# working.net
KiCad netlist of a schematic drawn in EAGLE
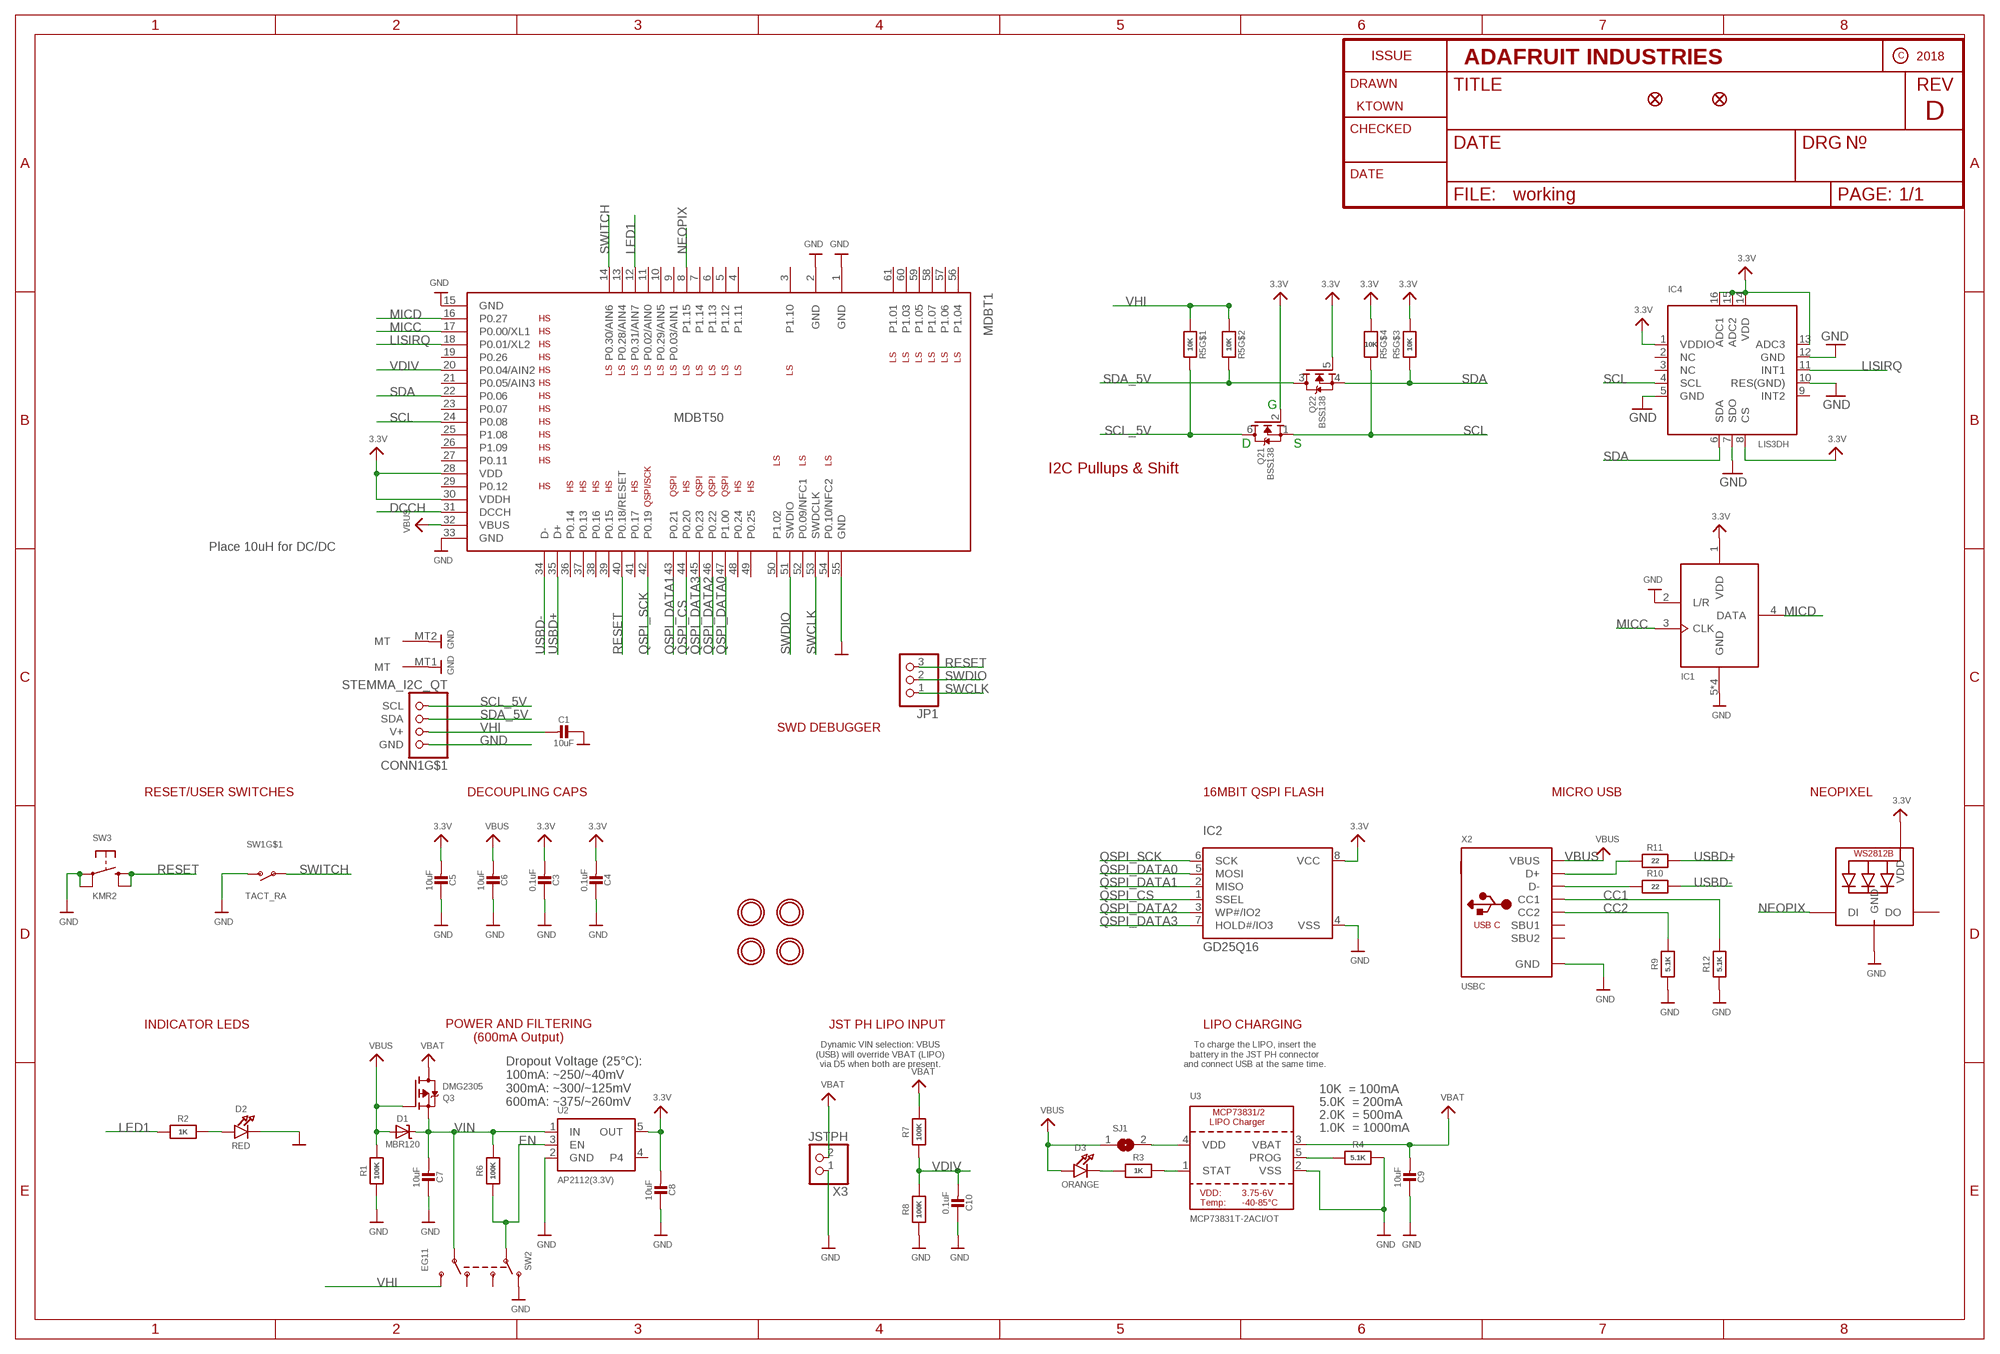
[diagram p0: schematic, sheet 1]

(export (version "E")
  (design (tool "Eeschema 10.0.6"))
  (components
    (comp (ref "C1")
      (value "10uF")
      (footprint "eagle-import:0805-NO")
      (libsource (lib "eagle-import") (part "CAP_CERAMIC0805-NOOUTLINE"))
    )
    (comp (ref "C3")
      (value "0.1uF")
      (footprint "eagle-import:0603-NO")
      (libsource (lib "eagle-import") (part "CAP_CERAMIC0603_NO"))
    )
    (comp (ref "C4")
      (value "0.1uF")
      (footprint "eagle-import:0603-NO")
      (libsource (lib "eagle-import") (part "CAP_CERAMIC0603_NO"))
    )
    (comp (ref "C5")
      (value "10uF")
      (footprint "eagle-import:0805-NO")
      (libsource (lib "eagle-import") (part "CAP_CERAMIC0805-NOOUTLINE"))
    )
    (comp (ref "C6")
      (value "10uF")
      (footprint "eagle-import:0805-NO")
      (libsource (lib "eagle-import") (part "CAP_CERAMIC0805-NOOUTLINE"))
    )
    (comp (ref "C7")
      (value "10uF")
      (footprint "eagle-import:0805-NO")
      (libsource (lib "eagle-import") (part "CAP_CERAMIC0805-NOOUTLINE"))
    )
    (comp (ref "C8")
      (value "10uF")
      (footprint "eagle-import:0805-NO")
      (libsource (lib "eagle-import") (part "CAP_CERAMIC0805-NOOUTLINE"))
    )
    (comp (ref "C9")
      (value "10uF")
      (footprint "eagle-import:0805-NO")
      (libsource (lib "eagle-import") (part "CAP_CERAMIC0805-NOOUTLINE"))
    )
    (comp (ref "C10")
      (value "0.1uF")
      (footprint "eagle-import:0603-NO")
      (libsource (lib "eagle-import") (part "CAP_CERAMIC0603_NO"))
    )
    (comp (ref "CONN1")
      (value "STEMMA_I2C_QT")
      (footprint "eagle-import:JST_SH4")
      (libsource (lib "eagle-import") (part "STEMMA_I2C_QT"))
    )
    (comp (ref "D1")
      (value "MBR120")
      (footprint "eagle-import:SOD-123")
      (libsource (lib "eagle-import") (part "DIODE-SCHOTTKYSOD-123"))
    )
    (comp (ref "D2")
      (value "RED")
      (footprint "eagle-import:CHIPLED_0805_NOOUTLINE")
      (libsource (lib "eagle-import") (part "LED0805_NOOUTLINE"))
    )
    (comp (ref "D3")
      (value "ORANGE")
      (footprint "eagle-import:CHIPLED_0805_NOOUTLINE")
      (libsource (lib "eagle-import") (part "LED0805_NOOUTLINE"))
    )
    (comp (ref "FID1")
      (value "FIDUCIAL_1MM")
      (footprint "eagle-import:FIDUCIAL_1MM")
      (libsource (lib "eagle-import") (part "FIDUCIAL_1MM"))
    )
    (comp (ref "FID2")
      (value "FIDUCIAL_1MM")
      (footprint "eagle-import:FIDUCIAL_1MM")
      (libsource (lib "eagle-import") (part "FIDUCIAL_1MM"))
    )
    (comp (ref "IC1")
      (value "MIC_PDM_SPK0415")
      (footprint "eagle-import:SPK0415HM4H")
      (libsource (lib "eagle-import") (part "MIC_PDM_SPK0415"))
    )
    (comp (ref "IC2")
      (value "GD25Q16")
      (footprint "eagle-import:SOIC8_150MIL")
      (libsource (lib "eagle-import") (part "SPIFLASH_8PIN"))
    )
    (comp (ref "IC4")
      (value "LIS3DH")
      (footprint "eagle-import:LGA16_3X3MM")
      (libsource (lib "eagle-import") (part "ACCEL_LIS3DHTR"))
    )
    (comp (ref "JP1")
      (value "HEADER-1X3ROUND")
      (footprint "eagle-import:1X03_ROUND")
      (libsource (lib "eagle-import") (part "HEADER-1X3ROUND"))
    )
    (comp (ref "LED1")
      (value "WS2812B_SK6805_1515")
      (footprint "eagle-import:SK6805_1515")
      (libsource (lib "eagle-import") (part "WS2812B_SK6805_1515"))
    )
    (comp (ref "MDBT1")
      (value "MDBT50")
      (footprint "eagle-import:MDBT50")
      (libsource (lib "eagle-import") (part "MDBT50"))
    )
    (comp (ref "Q2")
      (value "BSS138")
      (footprint "eagle-import:SOT363")
      (libsource (lib "eagle-import") (part "MOSFET-N_DUAL"))
    )
    (comp (ref "Q3")
      (value "DMG2305")
      (footprint "eagle-import:SOT23-R")
      (libsource (lib "eagle-import") (part "MOSFET-P"))
    )
    (comp (ref "R1")
      (value "100K")
      (footprint "eagle-import:0603-NO")
      (libsource (lib "eagle-import") (part "RESISTOR_0603_NOOUT"))
    )
    (comp (ref "R2")
      (value "1K")
      (footprint "eagle-import:0603-NO")
      (libsource (lib "eagle-import") (part "RESISTOR_0603_NOOUT"))
    )
    (comp (ref "R3")
      (value "1K")
      (footprint "eagle-import:0603-NO")
      (libsource (lib "eagle-import") (part "RESISTOR_0603_NOOUT"))
    )
    (comp (ref "R4")
      (value "5.1K")
      (footprint "eagle-import:0603-NO")
      (libsource (lib "eagle-import") (part "RESISTOR_0603_NOOUT"))
    )
    (comp (ref "R5")
      (value "10K")
      (footprint "eagle-import:RESPACK_4X0603")
      (libsource (lib "eagle-import") (part "RESISTOR_4PACK"))
    )
    (comp (ref "R6")
      (value "100K")
      (footprint "eagle-import:0603-NO")
      (libsource (lib "eagle-import") (part "RESISTOR_0603_NOOUT"))
    )
    (comp (ref "R7")
      (value "100K")
      (footprint "eagle-import:0603-NO")
      (libsource (lib "eagle-import") (part "RESISTOR_0603_NOOUT"))
    )
    (comp (ref "R8")
      (value "100K")
      (footprint "eagle-import:0603-NO")
      (libsource (lib "eagle-import") (part "RESISTOR_0603_NOOUT"))
    )
    (comp (ref "R9")
      (value "5.1K")
      (footprint "eagle-import:0603-NO")
      (libsource (lib "eagle-import") (part "RESISTOR_0603_NOOUT"))
    )
    (comp (ref "R10")
      (value "22")
      (footprint "eagle-import:0603-NO")
      (libsource (lib "eagle-import") (part "RESISTOR_0603_NOOUT"))
    )
    (comp (ref "R11")
      (value "22")
      (footprint "eagle-import:0603-NO")
      (libsource (lib "eagle-import") (part "RESISTOR_0603_NOOUT"))
    )
    (comp (ref "R12")
      (value "5.1K")
      (footprint "eagle-import:0603-NO")
      (libsource (lib "eagle-import") (part "RESISTOR_0603_NOOUT"))
    )
    (comp (ref "SJ1")
      (value "SOLDERJUMPER")
      (footprint "eagle-import:SOLDERJUMPER_ARROW_NOPASTE")
      (libsource (lib "eagle-import") (part "SOLDERJUMPER"))
    )
    (comp (ref "SW1")
      (value "TACT_RA")
      (footprint "eagle-import:SPST_TACTILE_RA")
      (libsource (lib "eagle-import") (part "SWITCH_SPST_TACT_RA"))
    )
    (comp (ref "SW2")
      (value "EG11")
      (footprint "eagle-import:EG1390")
      (libsource (lib "eagle-import") (part "SWITCH_DPDTEG1390"))
    )
    (comp (ref "SW3")
      (value "KMR2")
      (footprint "eagle-import:BTN_KMR2_4.6X2.8")
      (libsource (lib "eagle-import") (part "SWITCH_TACT_SMT4.6X2.8"))
    )
    (comp (ref "U$10")
      (value "MOUNTINGHOLE_SLOT4MM")
      (footprint "eagle-import:SLOT_4MM_PLATED")
      (libsource (lib "eagle-import") (part "MOUNTINGHOLE_SLOT4MM"))
    )
    (comp (ref "U$12")
      (value "MOUNTINGHOLE_SLOT4MM")
      (footprint "eagle-import:SLOT_4MM_PLATED")
      (libsource (lib "eagle-import") (part "MOUNTINGHOLE_SLOT4MM"))
    )
    (comp (ref "U$14")
      (value "MOUNTINGHOLE_SLOT4MM")
      (footprint "eagle-import:SLOT_4MM_PLATED")
      (libsource (lib "eagle-import") (part "MOUNTINGHOLE_SLOT4MM"))
    )
    (comp (ref "U$16")
      (value "MOUNTINGHOLE_SLOT4MM")
      (footprint "eagle-import:SLOT_4MM_PLATED")
      (libsource (lib "eagle-import") (part "MOUNTINGHOLE_SLOT4MM"))
    )
    (comp (ref "U2")
      (value "AP2112(3.3V)")
      (footprint "eagle-import:SOT23-5")
      (libsource (lib "eagle-import") (part "VREG_SOT23-5"))
    )
    (comp (ref "U3")
      (value "MCP73831T-2ACI/OT")
      (footprint "eagle-import:SOT23-5")
      (libsource (lib "eagle-import") (part "MCP73831/2"))
    )
    (comp (ref "X2")
      (value "USBC")
      (footprint "eagle-import:USB_C_CUSB31-CFM2AX-01-X")
      (libsource (lib "eagle-import") (part "USB_C"))
    )
    (comp (ref "X3")
      (value "JSTPH")
      (footprint "eagle-import:JSTPH2_BATT")
      (libsource (lib "eagle-import") (part "CON_JST_PH_2PIN_BATT"))
    )
  )
  (nets
    (net (code "1") (name "/CC1") (class "Default")
      (node (ref "R12") (pin "2") (pinfunction "2_2") (pintype "passive"))
      (node (ref "X2") (pin "A5") (pinfunction "CC1_A5") (pintype "bidirectional"))
    )
    (net (code "2") (name "/CC2") (class "Default")
      (node (ref "R9") (pin "2") (pinfunction "2_2") (pintype "passive"))
      (node (ref "X2") (pin "B5") (pinfunction "CC2_B5") (pintype "bidirectional"))
    )
    (net (code "3") (name "/DCCH") (class "Default")
      (node (ref "MDBT1") (pin "31") (pinfunction "DCCH_31") (pintype "bidirectional"))
    )
    (net (code "4") (name "/EN") (class "Default")
      (node (ref "R6") (pin "1") (pinfunction "1_1") (pintype "passive"))
      (node (ref "SW2") (pin "P1") (pinfunction "P1_P1") (pintype "passive"))
      (node (ref "U2") (pin "3") (pinfunction "EN_3") (pintype "input"))
    )
    (net (code "5") (name "/LED1") (class "Default")
      (node (ref "MDBT1") (pin "12") (pinfunction "P0.31/AIN7_12") (pintype "bidirectional"))
      (node (ref "R2") (pin "1") (pinfunction "1_1") (pintype "passive"))
    )
    (net (code "6") (name "/LISIRQ") (class "Default")
      (node (ref "IC4") (pin "11") (pinfunction "INT1_11") (pintype "output"))
      (node (ref "MDBT1") (pin "18") (pinfunction "P0.01/XL2_18") (pintype "bidirectional"))
    )
    (net (code "7") (name "/MICC") (class "Default")
      (node (ref "IC1") (pin "3") (pinfunction "CLK_3") (pintype "input"))
      (node (ref "MDBT1") (pin "17") (pinfunction "P0.00/XL1_17") (pintype "bidirectional"))
    )
    (net (code "8") (name "/MICD") (class "Default")
      (node (ref "IC1") (pin "4") (pinfunction "DATA_4") (pintype "bidirectional"))
      (node (ref "MDBT1") (pin "16") (pinfunction "P0.27_16") (pintype "bidirectional"))
    )
    (net (code "9") (name "/NEOPIX") (class "Default")
      (node (ref "LED1") (pin "1") (pinfunction "DI_1") (pintype "input"))
      (node (ref "MDBT1") (pin "8") (pinfunction "P1.15_8") (pintype "bidirectional"))
    )
    (net (code "10") (name "/QSPI_CS") (class "Default")
      (node (ref "IC2") (pin "1") (pinfunction "SSEL_1") (pintype "bidirectional"))
      (node (ref "MDBT1") (pin "44") (pinfunction "P0.20_44") (pintype "bidirectional"))
    )
    (net (code "11") (name "/QSPI_DATA0") (class "Default")
      (node (ref "IC2") (pin "5") (pinfunction "MOSI_5") (pintype "bidirectional"))
      (node (ref "MDBT1") (pin "47") (pinfunction "P1.00_47") (pintype "bidirectional"))
    )
    (net (code "12") (name "/QSPI_DATA1") (class "Default")
      (node (ref "IC2") (pin "2") (pinfunction "MISO_2") (pintype "bidirectional"))
      (node (ref "MDBT1") (pin "43") (pinfunction "P0.21_43") (pintype "bidirectional"))
    )
    (net (code "13") (name "/QSPI_DATA2") (class "Default")
      (node (ref "IC2") (pin "3") (pinfunction "WP#/IO2_3") (pintype "bidirectional"))
      (node (ref "MDBT1") (pin "46") (pinfunction "P0.22_46") (pintype "bidirectional"))
    )
    (net (code "14") (name "/QSPI_DATA3") (class "Default")
      (node (ref "IC2") (pin "7") (pinfunction "HOLD#/IO3_7") (pintype "bidirectional"))
      (node (ref "MDBT1") (pin "45") (pinfunction "P0.23_45") (pintype "bidirectional"))
    )
    (net (code "15") (name "/QSPI_SCK") (class "Default")
      (node (ref "IC2") (pin "6") (pinfunction "SCK_6") (pintype "bidirectional"))
      (node (ref "MDBT1") (pin "42") (pinfunction "P0.19_42") (pintype "bidirectional"))
    )
    (net (code "16") (name "/RESET") (class "Default")
      (node (ref "JP1") (pin "3") (pinfunction "3_3") (pintype "passive"))
      (node (ref "MDBT1") (pin "40") (pinfunction "P0.18/RESET_40") (pintype "bidirectional"))
      (node (ref "SW3") (pin "B") (pinfunction "S_B") (pintype "passive"))
      (node (ref "SW3") (pin "B'") (pinfunction "S1_B'") (pintype "passive"))
    )
    (net (code "17") (name "/SCL") (class "Default")
      (node (ref "IC4") (pin "4") (pinfunction "SCL_4") (pintype "bidirectional"))
      (node (ref "MDBT1") (pin "24") (pinfunction "P0.08_24") (pintype "bidirectional"))
      (node (ref "Q2") (pin "1") (pinfunction "S_1") (pintype "bidirectional"))
      (node (ref "R5") (pin "4") (pinfunction "1_4") (pintype "passive"))
    )
    (net (code "18") (name "/SCL_5V") (class "Default")
      (node (ref "CONN1") (pin "4") (pinfunction "SCL_4") (pintype "passive"))
      (node (ref "Q2") (pin "6") (pinfunction "D_6") (pintype "bidirectional"))
      (node (ref "R5") (pin "8") (pinfunction "2_8") (pintype "passive"))
    )
    (net (code "19") (name "/SDA") (class "Default")
      (node (ref "IC4") (pin "6") (pinfunction "SDA_6") (pintype "bidirectional"))
      (node (ref "MDBT1") (pin "22") (pinfunction "P0.06_22") (pintype "bidirectional"))
      (node (ref "Q2") (pin "4") (pinfunction "S_4") (pintype "bidirectional"))
      (node (ref "R5") (pin "6") (pinfunction "2_6") (pintype "passive"))
    )
    (net (code "20") (name "/SDA_5V") (class "Default")
      (node (ref "CONN1") (pin "3") (pinfunction "SDA_3") (pintype "passive"))
      (node (ref "Q2") (pin "3") (pinfunction "D_3") (pintype "bidirectional"))
      (node (ref "R5") (pin "7") (pinfunction "2_7") (pintype "passive"))
    )
    (net (code "21") (name "/SWCLK") (class "Default")
      (node (ref "JP1") (pin "1") (pinfunction "1_1") (pintype "passive"))
      (node (ref "MDBT1") (pin "53") (pinfunction "SWDCLK_53") (pintype "bidirectional"))
    )
    (net (code "22") (name "/SWDIO") (class "Default")
      (node (ref "JP1") (pin "2") (pinfunction "2_2") (pintype "passive"))
      (node (ref "MDBT1") (pin "51") (pinfunction "SWDIO_51") (pintype "bidirectional"))
    )
    (net (code "23") (name "/SWITCH") (class "Default")
      (node (ref "MDBT1") (pin "14") (pinfunction "P0.30/AIN6_14") (pintype "bidirectional"))
      (node (ref "SW1") (pin "1") (pinfunction "P_1") (pintype "passive"))
    )
    (net (code "24") (name "/USBD+") (class "Default")
      (node (ref "MDBT1") (pin "35") (pinfunction "D+_35") (pintype "bidirectional"))
      (node (ref "R11") (pin "2") (pinfunction "2_2") (pintype "passive"))
    )
    (net (code "25") (name "/USBD-") (class "Default")
      (node (ref "MDBT1") (pin "34") (pinfunction "D-_34") (pintype "bidirectional"))
      (node (ref "R10") (pin "2") (pinfunction "2_2") (pintype "passive"))
    )
    (net (code "26") (name "/VDIV") (class "Default")
      (node (ref "C10") (pin "2") (pinfunction "2_2") (pintype "passive"))
      (node (ref "MDBT1") (pin "20") (pinfunction "P0.04/AIN2_20") (pintype "bidirectional"))
      (node (ref "R7") (pin "1") (pinfunction "1_1") (pintype "passive"))
      (node (ref "R8") (pin "2") (pinfunction "2_2") (pintype "passive"))
    )
    (net (code "27") (name "/VHI") (class "Default")
      (node (ref "C1") (pin "2") (pinfunction "2_2") (pintype "passive"))
      (node (ref "CONN1") (pin "2") (pinfunction "V+_2") (pintype "passive"))
      (node (ref "R5") (pin "1") (pinfunction "1_1") (pintype "passive"))
      (node (ref "R5") (pin "2") (pinfunction "1_2") (pintype "passive"))
      (node (ref "SW2") (pin "S2") (pinfunction "S2_S2") (pintype "passive"))
    )
    (net (code "28") (name "/VIN") (class "Default")
      (node (ref "C7") (pin "2") (pinfunction "2_2") (pintype "passive"))
      (node (ref "D1") (pin "C") (pinfunction "C_C") (pintype "passive"))
      (node (ref "Q3") (pin "2") (pinfunction "S_2") (pintype "passive"))
      (node (ref "R6") (pin "2") (pinfunction "2_2") (pintype "passive"))
      (node (ref "SW2") (pin "P2") (pinfunction "P2_P2") (pintype "passive"))
      (node (ref "U2") (pin "1") (pinfunction "IN_1") (pintype "power_in"))
    )
    (net (code "29") (name "3.3V") (class "Default")
      (node (ref "C3") (pin "2") (pinfunction "2_2") (pintype "passive"))
      (node (ref "C4") (pin "2") (pinfunction "2_2") (pintype "passive"))
      (node (ref "C5") (pin "2") (pinfunction "2_2") (pintype "passive"))
      (node (ref "C8") (pin "2") (pinfunction "2_2") (pintype "passive"))
      (node (ref "IC1") (pin "1") (pinfunction "VDD_1") (pintype "power_in"))
      (node (ref "IC2") (pin "8") (pinfunction "VCC_8") (pintype "bidirectional"))
      (node (ref "IC4") (pin "1") (pinfunction "VDDIO_1") (pintype "power_in"))
      (node (ref "IC4") (pin "13") (pinfunction "ADC3_13") (pintype "input"))
      (node (ref "IC4") (pin "14") (pinfunction "VDD_14") (pintype "power_in"))
      (node (ref "IC4") (pin "15") (pinfunction "ADC2_15") (pintype "input"))
      (node (ref "IC4") (pin "16") (pinfunction "ADC1_16") (pintype "input"))
      (node (ref "IC4") (pin "8") (pinfunction "CS_8") (pintype "input"))
      (node (ref "LED1") (pin "2") (pinfunction "VDD_2") (pintype "power_in"))
      (node (ref "MDBT1") (pin "28") (pinfunction "VDD_28") (pintype "bidirectional"))
      (node (ref "MDBT1") (pin "30") (pinfunction "VDDH_30") (pintype "bidirectional"))
      (node (ref "Q2") (pin "2") (pinfunction "G_2") (pintype "bidirectional"))
      (node (ref "Q2") (pin "5") (pinfunction "G_5") (pintype "bidirectional"))
      (node (ref "R5") (pin "3") (pinfunction "1_3") (pintype "passive"))
      (node (ref "R5") (pin "5") (pinfunction "2_5") (pintype "passive"))
      (node (ref "U2") (pin "5") (pinfunction "OUT_5") (pintype "power_in"))
    )
    (net (code "30") (name "GND") (class "Default")
      (node (ref "C1") (pin "1") (pinfunction "1_1") (pintype "passive"))
      (node (ref "C10") (pin "1") (pinfunction "1_1") (pintype "passive"))
      (node (ref "C3") (pin "1") (pinfunction "1_1") (pintype "passive"))
      (node (ref "C4") (pin "1") (pinfunction "1_1") (pintype "passive"))
      (node (ref "C5") (pin "1") (pinfunction "1_1") (pintype "passive"))
      (node (ref "C6") (pin "1") (pinfunction "1_1") (pintype "passive"))
      (node (ref "C7") (pin "1") (pinfunction "1_1") (pintype "passive"))
      (node (ref "C8") (pin "1") (pinfunction "1_1") (pintype "passive"))
      (node (ref "C9") (pin "1") (pinfunction "1_1") (pintype "passive"))
      (node (ref "CONN1") (pin "1") (pinfunction "GND_1") (pintype "passive"))
      (node (ref "CONN1") (pin "MT1") (pinfunction "MT_MT1") (pintype "bidirectional"))
      (node (ref "CONN1") (pin "MT2") (pinfunction "MT_MT2") (pintype "bidirectional"))
      (node (ref "D2") (pin "C") (pinfunction "C_C") (pintype "passive"))
      (node (ref "IC1") (pin "2") (pinfunction "L/R_2") (pintype "input"))
      (node (ref "IC1") (pin "5") (pinfunction "GND_5") (pintype "power_in"))
      (node (ref "IC1") (pin "6") (pinfunction "GND_6") (pintype "power_in"))
      (node (ref "IC1") (pin "7") (pinfunction "GND_7") (pintype "power_in"))
      (node (ref "IC1") (pin "8") (pinfunction "GND_8") (pintype "power_in"))
      (node (ref "IC2") (pin "4") (pinfunction "VSS_4") (pintype "bidirectional"))
      (node (ref "IC4") (pin "10") (pinfunction "RES(GND)_10") (pintype "bidirectional"))
      (node (ref "IC4") (pin "12") (pinfunction "GND_12") (pintype "power_in"))
      (node (ref "IC4") (pin "5") (pinfunction "GND_5") (pintype "power_in"))
      (node (ref "IC4") (pin "7") (pinfunction "SDO_7") (pintype "bidirectional"))
      (node (ref "LED1") (pin "4") (pinfunction "GND_4") (pintype "power_in"))
      (node (ref "MDBT1") (pin "1") (pinfunction "GND_1") (pintype "bidirectional"))
      (node (ref "MDBT1") (pin "15") (pinfunction "GND_15") (pintype "bidirectional"))
      (node (ref "MDBT1") (pin "2") (pinfunction "GND_2") (pintype "bidirectional"))
      (node (ref "MDBT1") (pin "33") (pinfunction "GND_33") (pintype "bidirectional"))
      (node (ref "MDBT1") (pin "55") (pinfunction "GND_55") (pintype "bidirectional"))
      (node (ref "R1") (pin "1") (pinfunction "1_1") (pintype "passive"))
      (node (ref "R12") (pin "1") (pinfunction "1_1") (pintype "passive"))
      (node (ref "R4") (pin "2") (pinfunction "2_2") (pintype "passive"))
      (node (ref "R8") (pin "1") (pinfunction "1_1") (pintype "passive"))
      (node (ref "R9") (pin "1") (pinfunction "1_1") (pintype "passive"))
      (node (ref "SW1") (pin "2") (pinfunction "S_2") (pintype "passive"))
      (node (ref "SW2") (pin "O1") (pinfunction "O1_O1") (pintype "passive"))
      (node (ref "SW3") (pin "A") (pinfunction "P_A") (pintype "passive"))
      (node (ref "SW3") (pin "A'") (pinfunction "P1_A'") (pintype "passive"))
      (node (ref "U2") (pin "2") (pinfunction "GND_2") (pintype "power_in"))
      (node (ref "U3") (pin "2") (pinfunction "VSS_2") (pintype "power_in"))
      (node (ref "X2") (pin "A1B12") (pinfunction "GND_A1B12") (pintype "power_in"))
      (node (ref "X2") (pin "B1A12") (pinfunction "GND_B1A12") (pintype "power_in"))
      (node (ref "X3") (pin "1") (pinfunction "1_1") (pintype "passive"))
    )
    (net (code "31") (name "Net-(D2-PadA)") (class "Default")
      (node (ref "D2") (pin "A") (pinfunction "A_A") (pintype "passive"))
      (node (ref "R2") (pin "2") (pinfunction "2_2") (pintype "passive"))
    )
    (net (code "32") (name "Net-(D3-PadC)") (class "Default")
      (node (ref "D3") (pin "C") (pinfunction "C_C") (pintype "passive"))
      (node (ref "R3") (pin "1") (pinfunction "1_1") (pintype "passive"))
    )
    (net (code "33") (name "Net-(R10-Pad1)") (class "Default")
      (node (ref "R10") (pin "1") (pinfunction "1_1") (pintype "passive"))
      (node (ref "X2") (pin "A7") (pinfunction "D-_A7") (pintype "bidirectional"))
      (node (ref "X2") (pin "B7") (pinfunction "D-_B7") (pintype "bidirectional"))
    )
    (net (code "34") (name "Net-(R11-Pad1)") (class "Default")
      (node (ref "R11") (pin "1") (pinfunction "1_1") (pintype "passive"))
      (node (ref "X2") (pin "A6") (pinfunction "D+_A6") (pintype "bidirectional"))
      (node (ref "X2") (pin "B6") (pinfunction "D+_B6") (pintype "bidirectional"))
    )
    (net (code "35") (name "Net-(U3-PROG)") (class "Default")
      (node (ref "R4") (pin "1") (pinfunction "1_1") (pintype "passive"))
      (node (ref "U3") (pin "5") (pinfunction "PROG_5") (pintype "input"))
    )
    (net (code "36") (name "Net-(U3-STAT)") (class "Default")
      (node (ref "R3") (pin "2") (pinfunction "2_2") (pintype "passive"))
      (node (ref "U3") (pin "1") (pinfunction "STAT_1") (pintype "output"))
    )
    (net (code "37") (name "Net-(U3-VDD)") (class "Default")
      (node (ref "SJ1") (pin "2") (pinfunction "2_2") (pintype "passive"))
      (node (ref "U3") (pin "4") (pinfunction "VDD_4") (pintype "power_in"))
    )
    (net (code "38") (name "VBAT") (class "Default")
      (node (ref "C9") (pin "2") (pinfunction "2_2") (pintype "passive"))
      (node (ref "Q3") (pin "3") (pinfunction "D_3") (pintype "passive"))
      (node (ref "R7") (pin "2") (pinfunction "2_2") (pintype "passive"))
      (node (ref "U3") (pin "3") (pinfunction "VBAT_3") (pintype "power_in"))
      (node (ref "X3") (pin "2") (pinfunction "2_2") (pintype "passive"))
    )
    (net (code "39") (name "VBUS") (class "Default")
      (node (ref "C6") (pin "2") (pinfunction "2_2") (pintype "passive"))
      (node (ref "D1") (pin "A") (pinfunction "A_A") (pintype "passive"))
      (node (ref "D3") (pin "A") (pinfunction "A_A") (pintype "passive"))
      (node (ref "MDBT1") (pin "32") (pinfunction "VBUS_32") (pintype "bidirectional"))
      (node (ref "Q3") (pin "1") (pinfunction "G_1") (pintype "passive"))
      (node (ref "R1") (pin "2") (pinfunction "2_2") (pintype "passive"))
      (node (ref "SJ1") (pin "1") (pinfunction "1_1") (pintype "passive"))
      (node (ref "X2") (pin "A4B9") (pinfunction "VBUS_A4B9") (pintype "power_in"))
      (node (ref "X2") (pin "B4A9") (pinfunction "VBUS_B4A9") (pintype "power_in"))
    )
    (net (code "40") (name "unconnected-(IC4-INT2-Pad9)") (class "Default")
      (node (ref "IC4") (pin "9") (pinfunction "INT2_9") (pintype "output"))
    )
    (net (code "41") (name "unconnected-(IC4-NC-Pad2)") (class "Default")
      (node (ref "IC4") (pin "2") (pinfunction "NC_2") (pintype "no_connect"))
    )
    (net (code "42") (name "unconnected-(IC4-NC-Pad3)") (class "Default")
      (node (ref "IC4") (pin "3") (pinfunction "NC_3") (pintype "no_connect"))
    )
    (net (code "43") (name "unconnected-(LED1-DO-Pad3)") (class "Default")
      (node (ref "LED1") (pin "3") (pinfunction "DO_3") (pintype "output"))
    )
    (net (code "44") (name "unconnected-(MDBT1-P0.02{slash}AIN0-Pad11)") (class "Default")
      (node (ref "MDBT1") (pin "11") (pinfunction "P0.02/AIN0_11") (pintype "bidirectional"))
    )
    (net (code "45") (name "unconnected-(MDBT1-P0.03{slash}AIN1-Pad9)") (class "Default")
      (node (ref "MDBT1") (pin "9") (pinfunction "P0.03/AIN1_9") (pintype "bidirectional"))
    )
    (net (code "46") (name "unconnected-(MDBT1-P0.05{slash}AIN3-Pad21)") (class "Default")
      (node (ref "MDBT1") (pin "21") (pinfunction "P0.05/AIN3_21") (pintype "bidirectional"))
    )
    (net (code "47") (name "unconnected-(MDBT1-P0.07-Pad23)") (class "Default")
      (node (ref "MDBT1") (pin "23") (pinfunction "P0.07_23") (pintype "bidirectional"))
    )
    (net (code "48") (name "unconnected-(MDBT1-P0.09{slash}NFC1-Pad52)") (class "Default")
      (node (ref "MDBT1") (pin "52") (pinfunction "P0.09/NFC1_52") (pintype "bidirectional"))
    )
    (net (code "49") (name "unconnected-(MDBT1-P0.10{slash}NFC2-Pad54)") (class "Default")
      (node (ref "MDBT1") (pin "54") (pinfunction "P0.10/NFC2_54") (pintype "bidirectional"))
    )
    (net (code "50") (name "unconnected-(MDBT1-P0.11-Pad27)") (class "Default")
      (node (ref "MDBT1") (pin "27") (pinfunction "P0.11_27") (pintype "bidirectional"))
    )
    (net (code "51") (name "unconnected-(MDBT1-P0.12-Pad29)") (class "Default")
      (node (ref "MDBT1") (pin "29") (pinfunction "P0.12_29") (pintype "bidirectional"))
    )
    (net (code "52") (name "unconnected-(MDBT1-P0.13-Pad37)") (class "Default")
      (node (ref "MDBT1") (pin "37") (pinfunction "P0.13_37") (pintype "bidirectional"))
    )
    (net (code "53") (name "unconnected-(MDBT1-P0.14-Pad36)") (class "Default")
      (node (ref "MDBT1") (pin "36") (pinfunction "P0.14_36") (pintype "bidirectional"))
    )
    (net (code "54") (name "unconnected-(MDBT1-P0.15-Pad39)") (class "Default")
      (node (ref "MDBT1") (pin "39") (pinfunction "P0.15_39") (pintype "bidirectional"))
    )
    (net (code "55") (name "unconnected-(MDBT1-P0.16-Pad38)") (class "Default")
      (node (ref "MDBT1") (pin "38") (pinfunction "P0.16_38") (pintype "bidirectional"))
    )
    (net (code "56") (name "unconnected-(MDBT1-P0.17-Pad41)") (class "Default")
      (node (ref "MDBT1") (pin "41") (pinfunction "P0.17_41") (pintype "bidirectional"))
    )
    (net (code "57") (name "unconnected-(MDBT1-P0.24-Pad48)") (class "Default")
      (node (ref "MDBT1") (pin "48") (pinfunction "P0.24_48") (pintype "bidirectional"))
    )
    (net (code "58") (name "unconnected-(MDBT1-P0.25-Pad49)") (class "Default")
      (node (ref "MDBT1") (pin "49") (pinfunction "P0.25_49") (pintype "bidirectional"))
    )
    (net (code "59") (name "unconnected-(MDBT1-P0.26-Pad19)") (class "Default")
      (node (ref "MDBT1") (pin "19") (pinfunction "P0.26_19") (pintype "bidirectional"))
    )
    (net (code "60") (name "unconnected-(MDBT1-P0.28{slash}AIN4-Pad13)") (class "Default")
      (node (ref "MDBT1") (pin "13") (pinfunction "P0.28/AIN4_13") (pintype "bidirectional"))
    )
    (net (code "61") (name "unconnected-(MDBT1-P0.29{slash}AIN5-Pad10)") (class "Default")
      (node (ref "MDBT1") (pin "10") (pinfunction "P0.29/AIN5_10") (pintype "bidirectional"))
    )
    (net (code "62") (name "unconnected-(MDBT1-P1.01-Pad61)") (class "Default")
      (node (ref "MDBT1") (pin "61") (pinfunction "P1.01_61") (pintype "bidirectional"))
    )
    (net (code "63") (name "unconnected-(MDBT1-P1.02-Pad50)") (class "Default")
      (node (ref "MDBT1") (pin "50") (pinfunction "P1.02_50") (pintype "bidirectional"))
    )
    (net (code "64") (name "unconnected-(MDBT1-P1.03-Pad60)") (class "Default")
      (node (ref "MDBT1") (pin "60") (pinfunction "P1.03_60") (pintype "bidirectional"))
    )
    (net (code "65") (name "unconnected-(MDBT1-P1.04-Pad56)") (class "Default")
      (node (ref "MDBT1") (pin "56") (pinfunction "P1.04_56") (pintype "bidirectional"))
    )
    (net (code "66") (name "unconnected-(MDBT1-P1.05-Pad59)") (class "Default")
      (node (ref "MDBT1") (pin "59") (pinfunction "P1.05_59") (pintype "bidirectional"))
    )
    (net (code "67") (name "unconnected-(MDBT1-P1.06-Pad57)") (class "Default")
      (node (ref "MDBT1") (pin "57") (pinfunction "P1.06_57") (pintype "bidirectional"))
    )
    (net (code "68") (name "unconnected-(MDBT1-P1.07-Pad58)") (class "Default")
      (node (ref "MDBT1") (pin "58") (pinfunction "P1.07_58") (pintype "bidirectional"))
    )
    (net (code "69") (name "unconnected-(MDBT1-P1.08-Pad25)") (class "Default")
      (node (ref "MDBT1") (pin "25") (pinfunction "P1.08_25") (pintype "bidirectional"))
    )
    (net (code "70") (name "unconnected-(MDBT1-P1.09-Pad26)") (class "Default")
      (node (ref "MDBT1") (pin "26") (pinfunction "P1.09_26") (pintype "bidirectional"))
    )
    (net (code "71") (name "unconnected-(MDBT1-P1.10-Pad3)") (class "Default")
      (node (ref "MDBT1") (pin "3") (pinfunction "P1.10_3") (pintype "bidirectional"))
    )
    (net (code "72") (name "unconnected-(MDBT1-P1.11-Pad4)") (class "Default")
      (node (ref "MDBT1") (pin "4") (pinfunction "P1.11_4") (pintype "bidirectional"))
    )
    (net (code "73") (name "unconnected-(MDBT1-P1.12-Pad5)") (class "Default")
      (node (ref "MDBT1") (pin "5") (pinfunction "P1.12_5") (pintype "bidirectional"))
    )
    (net (code "74") (name "unconnected-(MDBT1-P1.13-Pad6)") (class "Default")
      (node (ref "MDBT1") (pin "6") (pinfunction "P1.13_6") (pintype "bidirectional"))
    )
    (net (code "75") (name "unconnected-(MDBT1-P1.14-Pad7)") (class "Default")
      (node (ref "MDBT1") (pin "7") (pinfunction "P1.14_7") (pintype "bidirectional"))
    )
    (net (code "76") (name "unconnected-(SW2-PadO2)") (class "Default")
      (node (ref "SW2") (pin "O2") (pinfunction "O2_O2") (pintype "passive"))
    )
    (net (code "77") (name "unconnected-(SW2-PadS1)") (class "Default")
      (node (ref "SW2") (pin "S1") (pinfunction "S1_S1") (pintype "passive"))
    )
    (net (code "78") (name "unconnected-(U2-P4-Pad4)") (class "Default")
      (node (ref "U2") (pin "4") (pinfunction "P4_4") (pintype "bidirectional"))
    )
    (net (code "79") (name "unconnected-(X2-SBU1-PadA8)") (class "Default")
      (node (ref "X2") (pin "A8") (pinfunction "SBU1_A8") (pintype "bidirectional"))
    )
    (net (code "80") (name "unconnected-(X2-SBU2-PadB8)") (class "Default")
      (node (ref "X2") (pin "B8") (pinfunction "SBU2_B8") (pintype "bidirectional"))
    )
  )
)
